# ConnectorsCircuit.net
KiCad netlist of a schematic drawn in Altium Designer
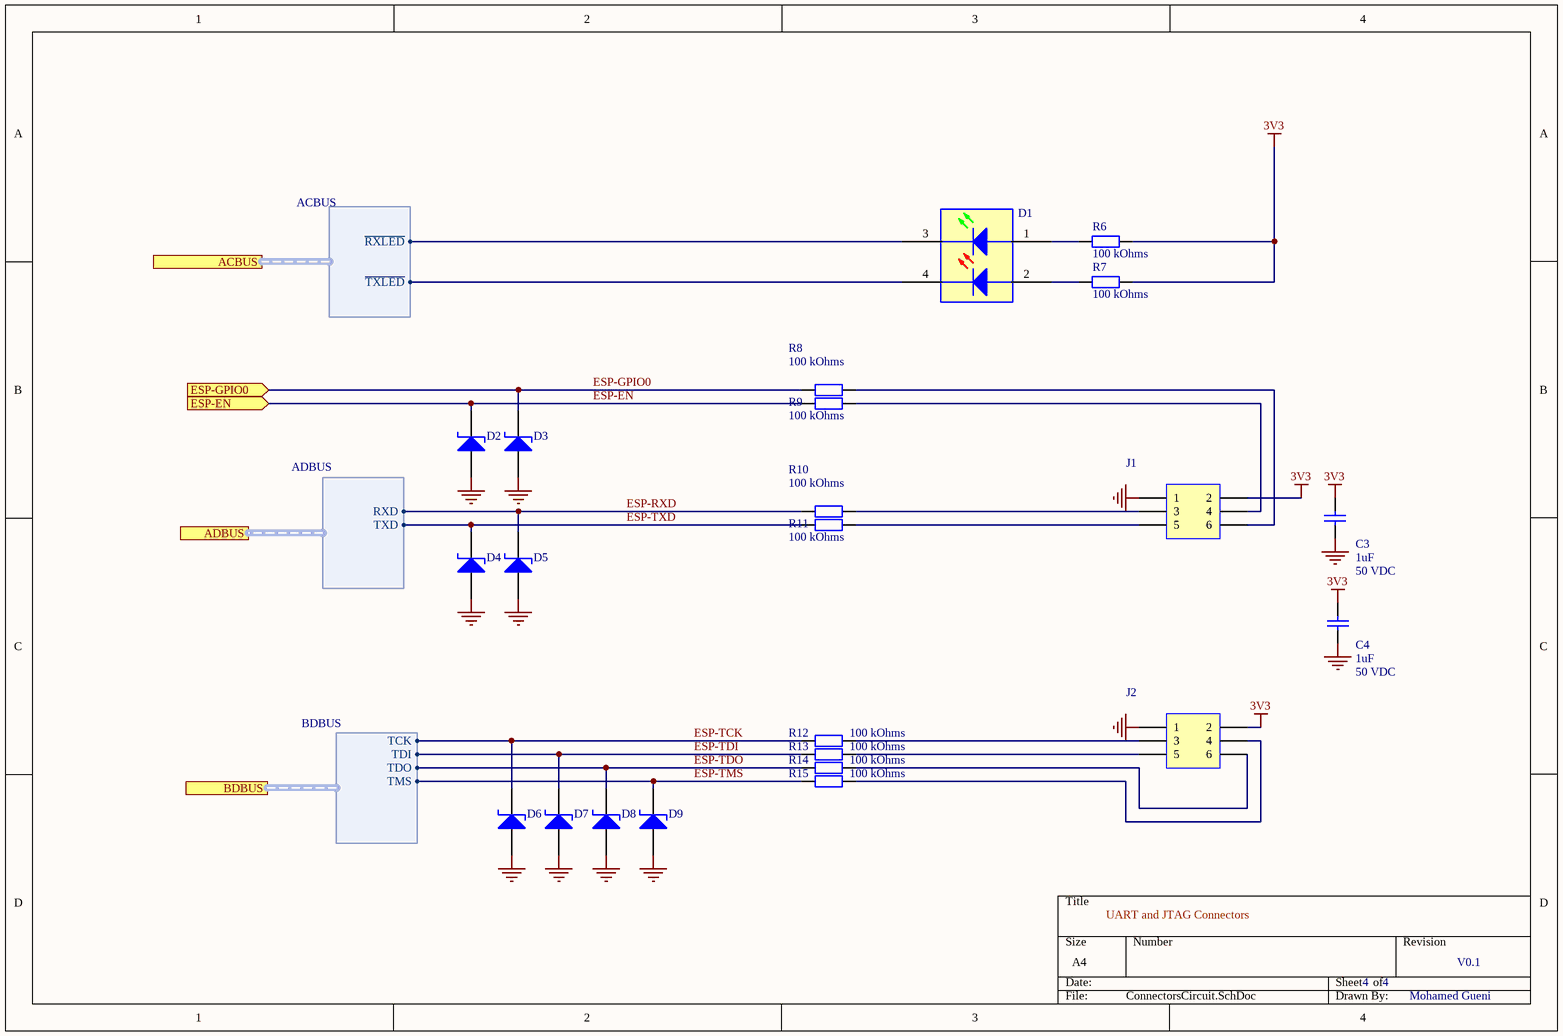
[diagram p0: ConnectorsCircuit.SchDoc]

(export (version "E")
  (design (tool "Eeschema 10.0.6"))
  (components
    (comp (ref "C3")
      (value "Capacitor")
      (footprint "CAP-0603")
      (fields
        (field (name "VALUE 1") "1uF")
        (field (name "VALUE 2") "50 VDC")
        (field (name "PART NUMBER") "C-000000011")
      )
      (libsource (lib "DATABASE") (part "Capacitor"))
    )
    (comp (ref "C4")
      (value "Capacitor")
      (footprint "CAP-0603")
      (fields
        (field (name "VALUE 1") "1uF")
        (field (name "VALUE 2") "50 VDC")
        (field (name "PART NUMBER") "C-000000011")
      )
      (libsource (lib "DATABASE") (part "Capacitor"))
    )
    (comp (ref "D1")
      (value "LTST-C155KGJRKT")
      (footprint "LTSTC155KGJRKT")
      (libsource (lib "DATABASE") (part "LED ARRAY"))
    )
    (comp (ref "D2")
      (value "ESD7351HT1G")
      (footprint "SOD-323-2")
      (fields (field (name "PART NUMBER") "D-000000004"))
      (libsource (lib "DATABASE") (part "TVS"))
    )
    (comp (ref "D3")
      (value "ESD7351HT1G")
      (footprint "SOD-323-2")
      (fields (field (name "PART NUMBER") "D-000000004"))
      (libsource (lib "DATABASE") (part "TVS"))
    )
    (comp (ref "D4")
      (value "ESD7351HT1G")
      (footprint "SOD-323-2")
      (fields (field (name "PART NUMBER") "D-000000004"))
      (libsource (lib "DATABASE") (part "TVS"))
    )
    (comp (ref "D5")
      (value "ESD7351HT1G")
      (footprint "SOD-323-2")
      (fields (field (name "PART NUMBER") "D-000000004"))
      (libsource (lib "DATABASE") (part "TVS"))
    )
    (comp (ref "D6")
      (value "ESD7351HT1G")
      (footprint "SOD-323-2")
      (fields (field (name "PART NUMBER") "D-000000004"))
      (libsource (lib "DATABASE") (part "TVS"))
    )
    (comp (ref "D7")
      (value "ESD7351HT1G")
      (footprint "SOD-323-2")
      (fields (field (name "PART NUMBER") "D-000000004"))
      (libsource (lib "DATABASE") (part "TVS"))
    )
    (comp (ref "D8")
      (value "ESD7351HT1G")
      (footprint "SOD-323-2")
      (fields (field (name "PART NUMBER") "D-000000004"))
      (libsource (lib "DATABASE") (part "TVS"))
    )
    (comp (ref "D9")
      (value "ESD7351HT1G")
      (footprint "SOD-323-2")
      (fields (field (name "PART NUMBER") "D-000000004"))
      (libsource (lib "DATABASE") (part "TVS"))
    )
    (comp (ref "J1")
      (value "Header 3X2")
      (footprint "SHDR6W75P200_2X3_865X640X650P")
      (fields (field (name "PART NUMBER") "J-000000001"))
      (libsource (lib "DATABASE") (part "Header 3X2"))
    )
    (comp (ref "J2")
      (value "Header 3X2")
      (footprint "SHDR6W75P200_2X3_865X640X650P")
      (fields (field (name "PART NUMBER") "J-000000001"))
      (libsource (lib "DATABASE") (part "Header 3X2"))
    )
    (comp (ref "R6")
      (value "Resistor")
      (footprint "R0603")
      (fields (field (name "VALUE 1") "100 kOhms") (field (name "PART NUMBER") "R-000000002"))
      (libsource (lib "DATABASE") (part "Resistor"))
    )
    (comp (ref "R7")
      (value "Resistor")
      (footprint "R0603")
      (fields (field (name "VALUE 1") "100 kOhms") (field (name "PART NUMBER") "R-000000002"))
      (libsource (lib "DATABASE") (part "Resistor"))
    )
    (comp (ref "R8")
      (value "Resistor")
      (footprint "R0603")
      (fields (field (name "VALUE 1") "100 kOhms") (field (name "PART NUMBER") "R-000000002"))
      (libsource (lib "DATABASE") (part "Resistor"))
    )
    (comp (ref "R9")
      (value "Resistor")
      (footprint "R0603")
      (fields (field (name "VALUE 1") "100 kOhms") (field (name "PART NUMBER") "R-000000002"))
      (libsource (lib "DATABASE") (part "Resistor"))
    )
    (comp (ref "R10")
      (value "Resistor")
      (footprint "R0603")
      (fields (field (name "VALUE 1") "100 kOhms") (field (name "PART NUMBER") "R-000000002"))
      (libsource (lib "DATABASE") (part "Resistor"))
    )
    (comp (ref "R11")
      (value "Resistor")
      (footprint "R0603")
      (fields (field (name "VALUE 1") "100 kOhms") (field (name "PART NUMBER") "R-000000002"))
      (libsource (lib "DATABASE") (part "Resistor"))
    )
    (comp (ref "R12")
      (value "Resistor")
      (footprint "R0603")
      (fields (field (name "VALUE 1") "100 kOhms") (field (name "PART NUMBER") "R-000000002"))
      (libsource (lib "DATABASE") (part "Resistor"))
    )
    (comp (ref "R13")
      (value "Resistor")
      (footprint "R0603")
      (fields (field (name "VALUE 1") "100 kOhms") (field (name "PART NUMBER") "R-000000002"))
      (libsource (lib "DATABASE") (part "Resistor"))
    )
    (comp (ref "R14")
      (value "Resistor")
      (footprint "R0603")
      (fields (field (name "VALUE 1") "100 kOhms") (field (name "PART NUMBER") "R-000000002"))
      (libsource (lib "DATABASE") (part "Resistor"))
    )
    (comp (ref "R15")
      (value "Resistor")
      (footprint "R0603")
      (fields (field (name "VALUE 1") "100 kOhms") (field (name "PART NUMBER") "R-000000002"))
      (libsource (lib "DATABASE") (part "Resistor"))
    )
  )
  (nets
    (net (code "4") (name "/ESP-EN") (class "Default")
      (node (ref "D2") (pin "2") (pinfunction "K1A2_2") (pintype "passive"))
      (node (ref "R9") (pin "1") (pinfunction "1_1") (pintype "passive"))
    )
    (net (code "5") (name "/ESP-GPIO0") (class "Default")
      (node (ref "D3") (pin "2") (pinfunction "K1A2_2") (pintype "passive"))
      (node (ref "R8") (pin "1") (pinfunction "1_1") (pintype "passive"))
    )
    (net (code "6") (name "/ESP-RXD") (class "Default")
      (node (ref "D5") (pin "2") (pinfunction "K1A2_2") (pintype "passive"))
      (node (ref "R10") (pin "1") (pinfunction "1_1") (pintype "passive"))
    )
    (net (code "7") (name "/ESP-TCK") (class "Default")
      (node (ref "D6") (pin "2") (pinfunction "K1A2_2") (pintype "passive"))
      (node (ref "R12") (pin "1") (pinfunction "1_1") (pintype "passive"))
    )
    (net (code "8") (name "/ESP-TDI") (class "Default")
      (node (ref "D7") (pin "2") (pinfunction "K1A2_2") (pintype "passive"))
      (node (ref "R13") (pin "1") (pinfunction "1_1") (pintype "passive"))
    )
    (net (code "9") (name "/ESP-TDO") (class "Default")
      (node (ref "D8") (pin "2") (pinfunction "K1A2_2") (pintype "passive"))
      (node (ref "R14") (pin "1") (pinfunction "1_1") (pintype "passive"))
    )
    (net (code "10") (name "/ESP-TMS") (class "Default")
      (node (ref "D9") (pin "2") (pinfunction "K1A2_2") (pintype "passive"))
      (node (ref "R15") (pin "1") (pinfunction "1_1") (pintype "passive"))
    )
    (net (code "11") (name "/ESP-TXD") (class "Default")
      (node (ref "D4") (pin "2") (pinfunction "K1A2_2") (pintype "passive"))
      (node (ref "R11") (pin "1") (pinfunction "1_1") (pintype "passive"))
    )
    (net (code "15") (name "/~{RXLED}") (class "Default")
      (node (ref "D1") (pin "3") (pinfunction "3_3") (pintype "passive"))
    )
    (net (code "16") (name "/~{TXLED}") (class "Default")
      (node (ref "D1") (pin "4") (pinfunction "4_4") (pintype "passive"))
    )
    (net (code "17") (name "3V3") (class "Default")
      (node (ref "C3") (pin "2") (pinfunction "2_2") (pintype "passive"))
      (node (ref "C4") (pin "2") (pinfunction "2_2") (pintype "passive"))
      (node (ref "J1") (pin "2") (pinfunction "2_2") (pintype "passive"))
      (node (ref "J2") (pin "2") (pinfunction "2_2") (pintype "passive"))
      (node (ref "R6") (pin "2") (pinfunction "2_2") (pintype "passive"))
      (node (ref "R7") (pin "2") (pinfunction "2_2") (pintype "passive"))
    )
    (net (code "18") (name "GND") (class "Default")
      (node (ref "C3") (pin "1") (pinfunction "1_1") (pintype "passive"))
      (node (ref "C4") (pin "1") (pinfunction "1_1") (pintype "passive"))
      (node (ref "D2") (pin "1") (pinfunction "1_1") (pintype "passive"))
      (node (ref "D3") (pin "1") (pinfunction "1_1") (pintype "passive"))
      (node (ref "D4") (pin "1") (pinfunction "1_1") (pintype "passive"))
      (node (ref "D5") (pin "1") (pinfunction "1_1") (pintype "passive"))
      (node (ref "D6") (pin "1") (pinfunction "1_1") (pintype "passive"))
      (node (ref "D7") (pin "1") (pinfunction "1_1") (pintype "passive"))
      (node (ref "D8") (pin "1") (pinfunction "1_1") (pintype "passive"))
      (node (ref "D9") (pin "1") (pinfunction "1_1") (pintype "passive"))
      (node (ref "J1") (pin "1") (pinfunction "1_1") (pintype "passive"))
      (node (ref "J2") (pin "1") (pinfunction "1_1") (pintype "passive"))
    )
    (net (code "19") (name "Net-(D1-Pad1)") (class "Default")
      (node (ref "D1") (pin "1") (pinfunction "1_1") (pintype "passive"))
      (node (ref "R6") (pin "1") (pinfunction "1_1") (pintype "passive"))
    )
    (net (code "20") (name "Net-(D1-Pad2)") (class "Default")
      (node (ref "D1") (pin "2") (pinfunction "2_2") (pintype "passive"))
      (node (ref "R7") (pin "1") (pinfunction "1_1") (pintype "passive"))
    )
    (net (code "21") (name "Net-(J1-Pad3)") (class "Default")
      (node (ref "J1") (pin "3") (pinfunction "3_3") (pintype "passive"))
      (node (ref "R10") (pin "2") (pinfunction "2_2") (pintype "passive"))
    )
    (net (code "22") (name "Net-(J1-Pad4)") (class "Default")
      (node (ref "J1") (pin "4") (pinfunction "4_4") (pintype "passive"))
      (node (ref "R9") (pin "2") (pinfunction "2_2") (pintype "passive"))
    )
    (net (code "23") (name "Net-(J1-Pad5)") (class "Default")
      (node (ref "J1") (pin "5") (pinfunction "5_5") (pintype "passive"))
      (node (ref "R11") (pin "2") (pinfunction "2_2") (pintype "passive"))
    )
    (net (code "24") (name "Net-(J1-Pad6)") (class "Default")
      (node (ref "J1") (pin "6") (pinfunction "6_6") (pintype "passive"))
      (node (ref "R8") (pin "2") (pinfunction "2_2") (pintype "passive"))
    )
    (net (code "25") (name "Net-(J2-Pad3)") (class "Default")
      (node (ref "J2") (pin "3") (pinfunction "3_3") (pintype "passive"))
      (node (ref "R12") (pin "2") (pinfunction "2_2") (pintype "passive"))
    )
    (net (code "26") (name "Net-(J2-Pad4)") (class "Default")
      (node (ref "J2") (pin "4") (pinfunction "4_4") (pintype "passive"))
      (node (ref "R15") (pin "2") (pinfunction "2_2") (pintype "passive"))
    )
    (net (code "27") (name "Net-(J2-Pad5)") (class "Default")
      (node (ref "J2") (pin "5") (pinfunction "5_5") (pintype "passive"))
      (node (ref "R13") (pin "2") (pinfunction "2_2") (pintype "passive"))
    )
    (net (code "28") (name "Net-(J2-Pad6)") (class "Default")
      (node (ref "J2") (pin "6") (pinfunction "6_6") (pintype "passive"))
      (node (ref "R14") (pin "2") (pinfunction "2_2") (pintype "passive"))
    )
  )
)
